# 05_power.net
KiCad netlist of a schematic drawn in Altium Designer
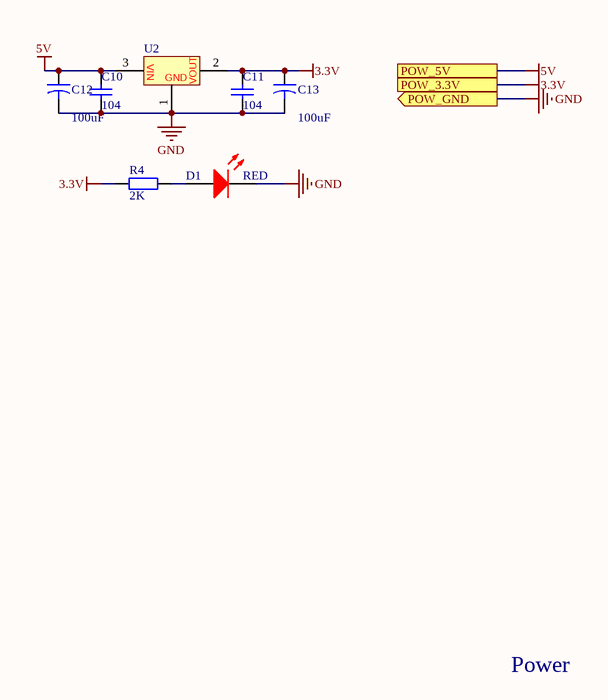
[diagram p0: 05.power.SchDoc]

(export (version "E")
  (design (tool "Eeschema 10.0.6"))
  (components
    (comp (ref "C10")
      (value "104")
      (footprint "0603C")
      (description "Capacitor")
      (fields (field (name "PUBLISHER") "Altium Limited"))
      (libsource (lib "My_Library") (part "Cap"))
    )
    (comp (ref "C11")
      (value "104")
      (footprint "0603C")
      (description "Capacitor")
      (fields (field (name "PUBLISHER") "Altium Limited"))
      (libsource (lib "My_Library") (part "Cap"))
    )
    (comp (ref "C12")
      (value "100uF")
      (footprint "3216")
      (description "Capacitor")
      (fields (field (name "Comment") "Cap2") (field (name "PUBLISHER") "Altium Limited"))
      (libsource (lib "My_Library") (part "Cap2"))
    )
    (comp (ref "C13")
      (value "100uF")
      (footprint "3216")
      (description "Capacitor")
      (fields (field (name "Comment") "Cap2") (field (name "PUBLISHER") "Altium Limited"))
      (libsource (lib "My_Library") (part "Cap2"))
    )
    (comp (ref "D1")
      (value "RED")
      (footprint "0603led")
      (description "Typical RED")
      (fields (field (name "PUBLISHER") "Altium Limited"))
      (libsource (lib "My_Library") (part "LED_RED"))
    )
    (comp (ref "R4")
      (value "2K")
      (footprint "0603R")
      (description "Resistor")
      (fields (field (name "Comment") "Res2") (field (name "PUBLISHER") "Altium Limited"))
      (libsource (lib "My_Library") (part "Res2"))
    )
    (comp (ref "U2") (value "~") (footprint "sot-89") (libsource (lib "My_Library") (part "AMS1117")))
  )
  (nets
    (net (code "1") (name "3.3V") (class "Default")
      (node (ref "C11") (pin "2") (pinfunction "2_2") (pintype "passive"))
      (node (ref "C13") (pin "1") (pinfunction "1_1") (pintype "passive"))
      (node (ref "R4") (pin "1") (pinfunction "1_1") (pintype "passive"))
      (node (ref "U2") (pin "2") (pinfunction "VOUT_2") (pintype "passive"))
    )
    (net (code "2") (name "5V") (class "Default")
      (node (ref "C10") (pin "2") (pinfunction "2_2") (pintype "passive"))
      (node (ref "C12") (pin "1") (pinfunction "1_1") (pintype "passive"))
      (node (ref "U2") (pin "3") (pinfunction "VIN_3") (pintype "passive"))
    )
    (net (code "3") (name "GND") (class "Default")
      (node (ref "C10") (pin "1") (pinfunction "1_1") (pintype "passive"))
      (node (ref "C11") (pin "1") (pinfunction "1_1") (pintype "passive"))
      (node (ref "C12") (pin "2") (pinfunction "2_2") (pintype "passive"))
      (node (ref "C13") (pin "2") (pinfunction "2_2") (pintype "passive"))
      (node (ref "D1") (pin "2") (pinfunction "2_2") (pintype "passive"))
      (node (ref "U2") (pin "1") (pinfunction "GND_1") (pintype "passive"))
    )
    (net (code "4") (name "Net-(D1-Pad1)") (class "Default")
      (node (ref "D1") (pin "1") (pinfunction "1_1") (pintype "passive"))
      (node (ref "R4") (pin "2") (pinfunction "2_2") (pintype "passive"))
    )
  )
)
